# connectors.net
KiCad netlist of a schematic drawn in Altium Designer
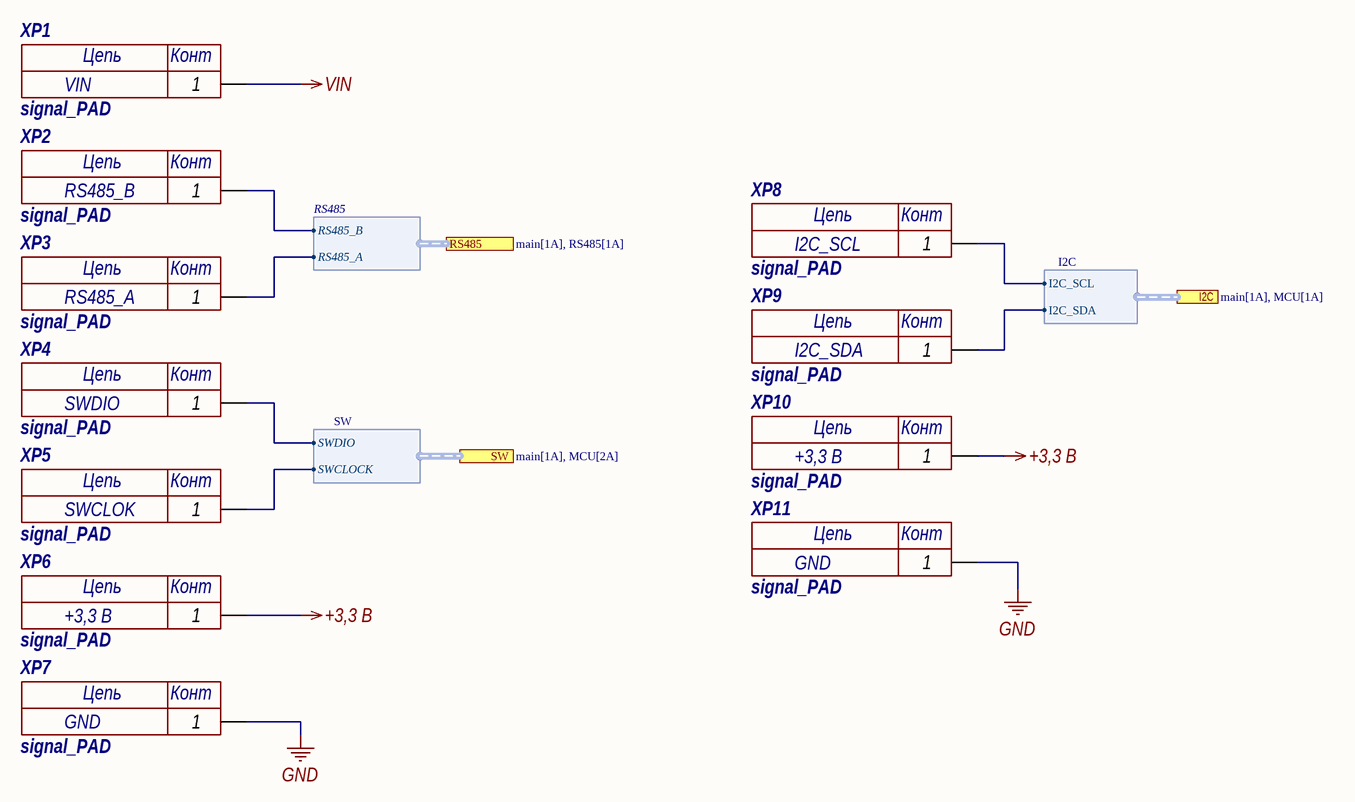
[diagram p0: connectors.SchDoc]

(export (version "E")
  (design (tool "Eeschema 10.0.6"))
  (components
    (comp (ref "XP1")
      (value "signal_PAD")
      (footprint "SS_PAD")
      (description "контактная площадка под пайку тонких проводов")
      (fields (field (name "VALUE1") "VIN"))
      (libsource (lib "Hydrolib") (part "Conn_1pin"))
    )
    (comp (ref "XP2")
      (value "signal_PAD")
      (footprint "SS_PAD")
      (description "контактная площадка под пайку тонких проводов")
      (fields (field (name "VALUE1") "RS485_B"))
      (libsource (lib "Hydrolib") (part "Conn_1pin"))
    )
    (comp (ref "XP3")
      (value "signal_PAD")
      (footprint "SS_PAD")
      (description "контактная площадка под пайку тонких проводов")
      (fields (field (name "VALUE1") "RS485_A"))
      (libsource (lib "Hydrolib") (part "Conn_1pin"))
    )
    (comp (ref "XP4")
      (value "signal_PAD")
      (footprint "SS_PAD")
      (description "контактная площадка под пайку тонких проводов")
      (fields (field (name "VALUE1") "SWDIO"))
      (libsource (lib "Hydrolib") (part "Conn_1pin"))
    )
    (comp (ref "XP5")
      (value "signal_PAD")
      (footprint "SS_PAD")
      (description "контактная площадка под пайку тонких проводов")
      (fields (field (name "VALUE1") "SWCLOK"))
      (libsource (lib "Hydrolib") (part "Conn_1pin"))
    )
    (comp (ref "XP6")
      (value "signal_PAD")
      (footprint "SS_PAD")
      (description "контактная площадка под пайку тонких проводов")
      (fields (field (name "VALUE1") "+3,3 В"))
      (libsource (lib "Hydrolib") (part "Conn_1pin"))
    )
    (comp (ref "XP7")
      (value "signal_PAD")
      (footprint "SS_PAD")
      (description "контактная площадка под пайку тонких проводов")
      (fields (field (name "VALUE1") "GND"))
      (libsource (lib "Hydrolib") (part "Conn_1pin"))
    )
    (comp (ref "XP8")
      (value "signal_PAD")
      (footprint "SS_PAD")
      (description "контактная площадка под пайку тонких проводов")
      (fields (field (name "VALUE1") "I2C_SCL"))
      (libsource (lib "Hydrolib") (part "Conn_1pin"))
    )
    (comp (ref "XP9")
      (value "signal_PAD")
      (footprint "SS_PAD")
      (description "контактная площадка под пайку тонких проводов")
      (fields (field (name "VALUE1") "I2C_SDA"))
      (libsource (lib "Hydrolib") (part "Conn_1pin"))
    )
    (comp (ref "XP10")
      (value "signal_PAD")
      (footprint "SS_PAD")
      (description "контактная площадка под пайку тонких проводов")
      (fields (field (name "VALUE1") "+3,3 В"))
      (libsource (lib "Hydrolib") (part "Conn_1pin"))
    )
    (comp (ref "XP11")
      (value "signal_PAD")
      (footprint "SS_PAD")
      (description "контактная площадка под пайку тонких проводов")
      (fields (field (name "VALUE1") "GND"))
      (libsource (lib "Hydrolib") (part "Conn_1pin"))
    )
  )
  (nets
    (net (code "4") (name "+3,3 В") (class "Default")
      (node (ref "XP10") (pin "1") (pinfunction "1_1") (pintype "passive"))
      (node (ref "XP6") (pin "1") (pinfunction "1_1") (pintype "passive"))
    )
    (net (code "5") (name "/I2C_SCL") (class "Default")
      (node (ref "XP8") (pin "1") (pinfunction "1_1") (pintype "passive"))
    )
    (net (code "6") (name "/I2C_SDA") (class "Default")
      (node (ref "XP9") (pin "1") (pinfunction "1_1") (pintype "passive"))
    )
    (net (code "7") (name "/RS485_A") (class "Default")
      (node (ref "XP3") (pin "1") (pinfunction "1_1") (pintype "passive"))
    )
    (net (code "8") (name "/RS485_B") (class "Default")
      (node (ref "XP2") (pin "1") (pinfunction "1_1") (pintype "passive"))
    )
    (net (code "9") (name "/SWCLOCK") (class "Default")
      (node (ref "XP5") (pin "1") (pinfunction "1_1") (pintype "passive"))
    )
    (net (code "10") (name "/SWDIO") (class "Default")
      (node (ref "XP4") (pin "1") (pinfunction "1_1") (pintype "passive"))
    )
    (net (code "14") (name "GND") (class "Default")
      (node (ref "XP11") (pin "1") (pinfunction "1_1") (pintype "passive"))
      (node (ref "XP7") (pin "1") (pinfunction "1_1") (pintype "passive"))
    )
    (net (code "15") (name "VIN") (class "Default")
      (node (ref "XP1") (pin "1") (pinfunction "1_1") (pintype "passive"))
    )
  )
)
